# TOF.net
KiCad netlist of a schematic drawn in Altium Designer
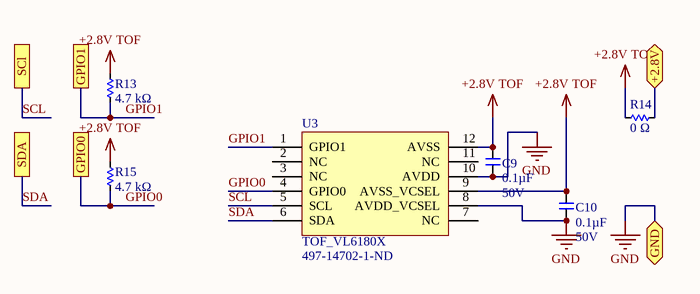
[diagram p0: TOF.SchDoc]

(export (version "E")
  (design (tool "Eeschema 10.0.6"))
  (components
    (comp (ref "C9")
      (value "__template_cap")
      (footprint "C0603")
      (fields
        (field (name "CAPACITANCE (SHORTHAND)") "0.1µF")
        (field (name "RATED VOLTAGE") "50V")
        (field (name "MANUFACTURER") "Murata Electronics North America")
      )
      (libsource (lib "passives") (part "__template_cap"))
    )
    (comp (ref "C10")
      (value "__template_cap")
      (footprint "C0603")
      (fields
        (field (name "CAPACITANCE (SHORTHAND)") "0.1µF")
        (field (name "RATED VOLTAGE") "50V")
        (field (name "MANUFACTURER") "Murata Electronics North America")
      )
      (libsource (lib "passives") (part "__template_cap"))
    )
    (comp (ref "R13")
      (value "__template_resistor")
      (footprint "R0805")
      (fields
        (field (name "RESISTANCE") "4.7 kΩ")
        (field (name "MANUFACTURER PART NUMBER") "RC0805FR-074K7L")
        (field (name "MANUFACTURER") "Yageo")
        (field (name "TOLERANCE") "±1%")
      )
      (libsource (lib "passives") (part "__template_resistor"))
    )
    (comp (ref "R14")
      (value "__template_resistor")
      (footprint "R0805")
      (fields
        (field (name "RESISTANCE") "0 Ω")
        (field (name "MANUFACTURER PART NUMBER") "RC0805FR-070RL")
        (field (name "MANUFACTURER") "Yageo")
        (field (name "TOLERANCE") "Jumper")
      )
      (libsource (lib "passives") (part "__template_resistor"))
    )
    (comp (ref "R15")
      (value "__template_resistor")
      (footprint "R0805")
      (fields
        (field (name "RESISTANCE") "4.7 kΩ")
        (field (name "MANUFACTURER PART NUMBER") "RC0805FR-074K7L")
        (field (name "MANUFACTURER") "Yageo")
        (field (name "TOLERANCE") "±1%")
      )
      (libsource (lib "passives") (part "__template_resistor"))
    )
    (comp (ref "U3")
      (value "TOF_VL6180X")
      (footprint "TOF_VL6180X")
      (description "Proximity and ambient light sensing (ALS) module")
      (fields
        (field (name "MANUFACTURER") "STMicroelectronics")
        (field (name "MANUFACTURER PART NUMBER") "VL6180XV0NR/1")
        (field (name "SUPPLIER PART NUMBER 1") "497-14702-1-ND")
      )
      (libsource (lib "SSI") (part "TOF_VL6180X"))
    )
  )
  (nets
    (net (code "1") (name "+2.8V TOF") (class "Default")
      (node (ref "C10") (pin "1") (pintype "passive"))
      (node (ref "C9") (pin "1") (pintype "passive"))
      (node (ref "R13") (pin "2") (pintype "passive"))
      (node (ref "R14") (pin "1") (pintype "passive"))
      (node (ref "R15") (pin "2") (pintype "passive"))
      (node (ref "U3") (pin "12") (pinfunction "AVSS_12") (pintype "power_in"))
      (node (ref "U3") (pin "9") (pinfunction "AVSS_VCSEL_9") (pintype "power_in"))
    )
    (net (code "2") (name "/+2.8V") (class "Default") (node (ref "R14") (pin "2") (pintype "passive")))
    (net (code "3") (name "/GPIO0") (class "Default")
      (node (ref "R15") (pin "1") (pintype "passive"))
      (node (ref "U3") (pin "4") (pinfunction "GPIO0_4") (pintype "power_in"))
    )
    (net (code "4") (name "/GPIO1") (class "Default")
      (node (ref "R13") (pin "1") (pintype "passive"))
      (node (ref "U3") (pin "1") (pinfunction "GPIO1_1") (pintype "power_in"))
    )
    (net (code "5") (name "/SCL") (class "Default")
      (node (ref "U3") (pin "5") (pinfunction "SCL_5") (pintype "power_in"))
    )
    (net (code "6") (name "/SDA") (class "Default")
      (node (ref "U3") (pin "6") (pinfunction "SDA_6") (pintype "power_in"))
    )
    (net (code "7") (name "GND") (class "Default")
      (node (ref "C10") (pin "2") (pintype "passive"))
      (node (ref "C9") (pin "2") (pintype "passive"))
      (node (ref "U3") (pin "10") (pinfunction "AVDD_10") (pintype "power_in"))
      (node (ref "U3") (pin "8") (pinfunction "AVDD_VCSEL_8") (pintype "power_in"))
    )
    (net (code "8") (name "unconnected-(U3-NC-Pad2)") (class "Default")
      (node (ref "U3") (pin "2") (pinfunction "NC_2") (pintype "power_in"))
    )
    (net (code "9") (name "unconnected-(U3-NC-Pad3)") (class "Default")
      (node (ref "U3") (pin "3") (pinfunction "NC_3") (pintype "power_in"))
    )
    (net (code "10") (name "unconnected-(U3-NC-Pad7)") (class "Default")
      (node (ref "U3") (pin "7") (pinfunction "NC_7") (pintype "power_in"))
    )
    (net (code "11") (name "unconnected-(U3-NC-Pad11)") (class "Default")
      (node (ref "U3") (pin "11") (pinfunction "NC_11") (pintype "power_in"))
    )
  )
)
